# Adafrruit_PCF8523_QT.net
KiCad netlist of a schematic drawn in EAGLE
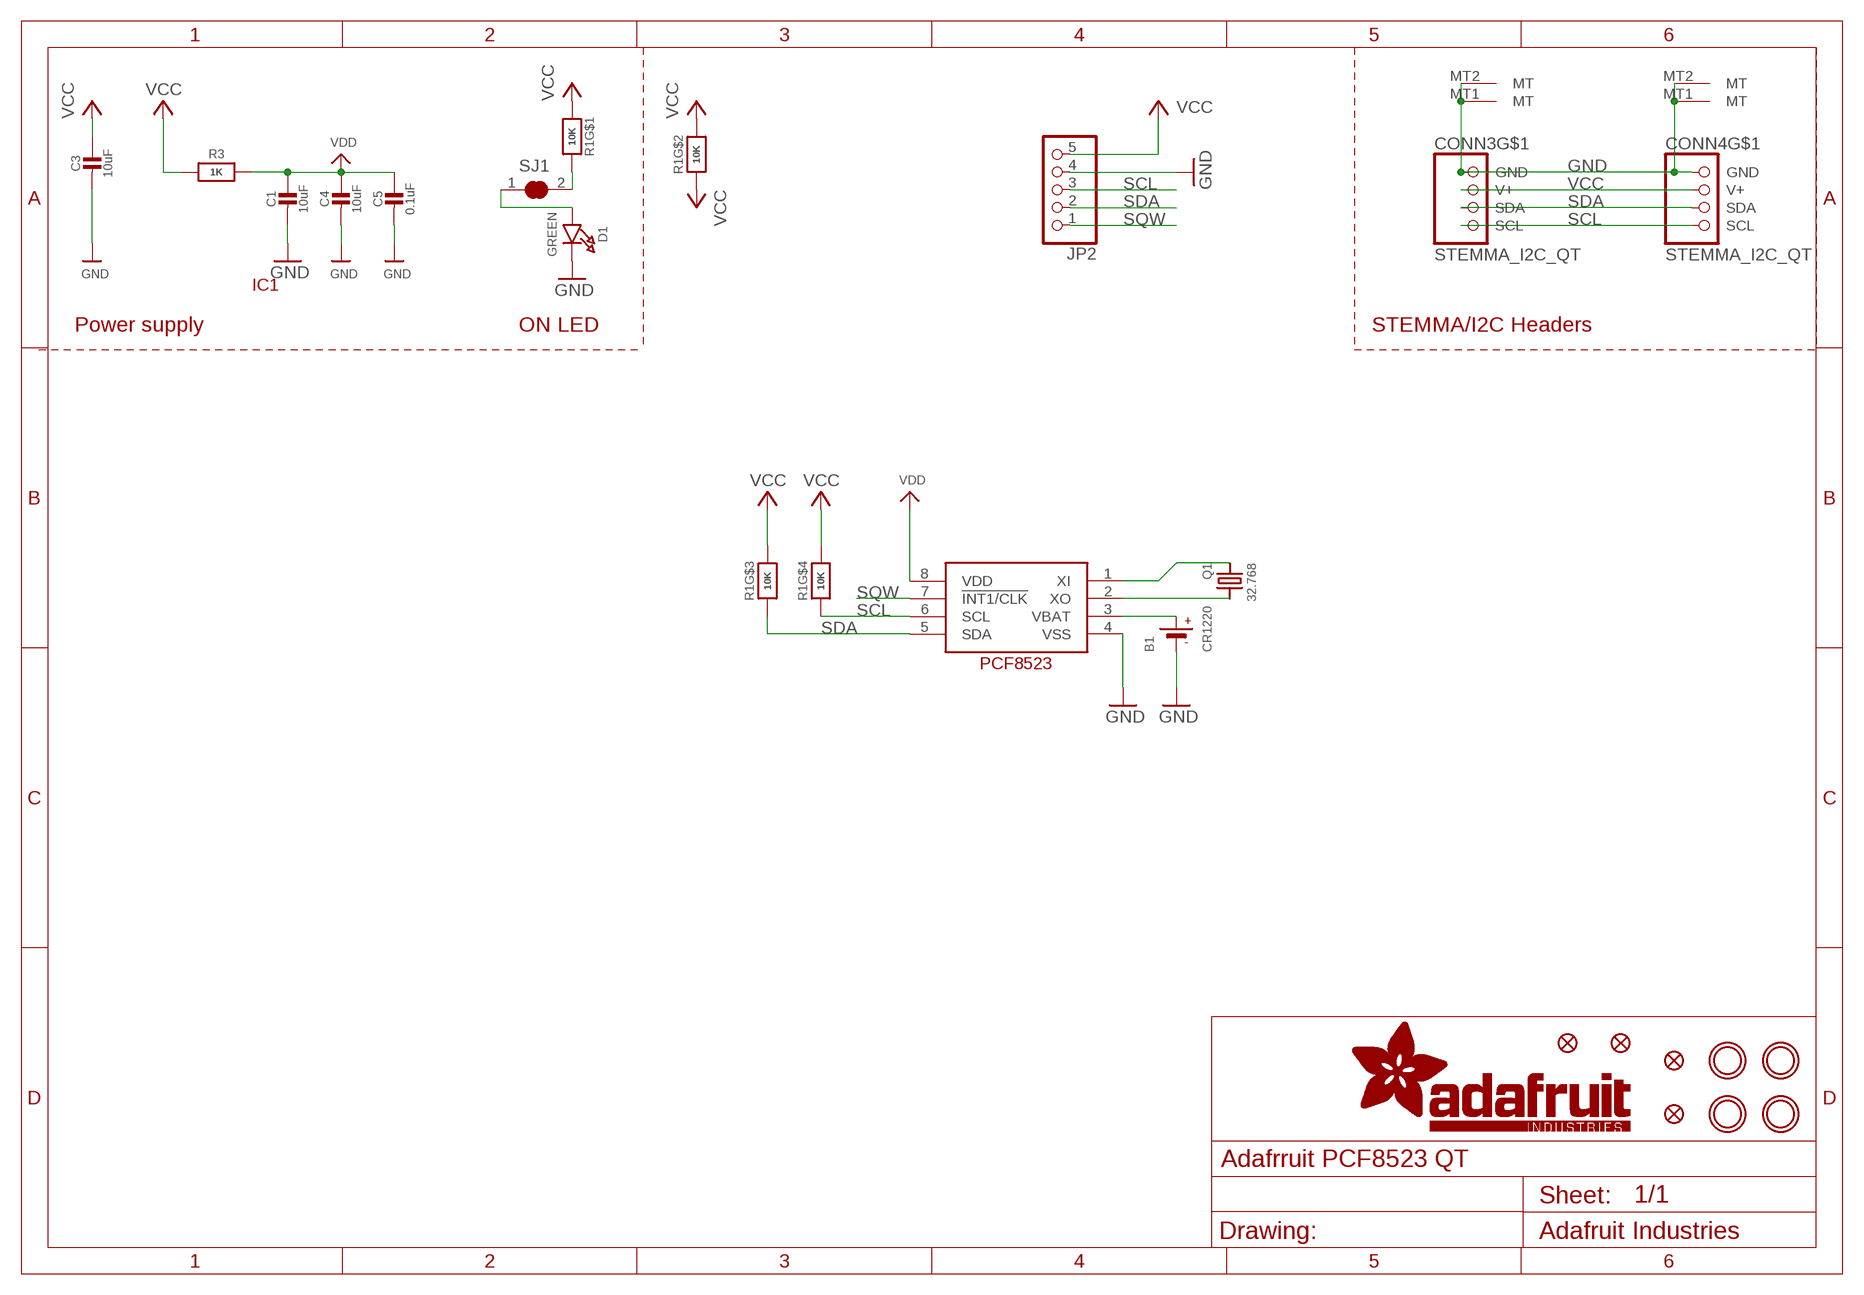
[diagram p0: schematic, sheet 1]

(export (version "E")
  (design (tool "Eeschema 10.0.6"))
  (components
    (comp (ref "B1")
      (value "CR1220")
      (footprint "eagle-import:CR1220")
      (libsource (lib "eagle-import") (part "BATTERYCR1220_SMT"))
    )
    (comp (ref "C1")
      (value "10uF")
      (footprint "eagle-import:0805-NO")
      (libsource (lib "eagle-import") (part "CAP_CERAMIC0805-NOOUTLINE"))
    )
    (comp (ref "C3")
      (value "10uF")
      (footprint "eagle-import:0805-NO")
      (libsource (lib "eagle-import") (part "CAP_CERAMIC0805-NOOUTLINE"))
    )
    (comp (ref "C4")
      (value "10uF")
      (footprint "eagle-import:0805-NO")
      (libsource (lib "eagle-import") (part "CAP_CERAMIC0805-NOOUTLINE"))
    )
    (comp (ref "C5")
      (value "0.1uF")
      (footprint "eagle-import:0603-NO")
      (libsource (lib "eagle-import") (part "CAP_CERAMIC0603_NO"))
    )
    (comp (ref "CONN3")
      (value "STEMMA_I2C_QT")
      (footprint "eagle-import:JST_SH4")
      (libsource (lib "eagle-import") (part "STEMMA_I2C_QT"))
    )
    (comp (ref "CONN4")
      (value "STEMMA_I2C_QT")
      (footprint "eagle-import:JST_SH4")
      (libsource (lib "eagle-import") (part "STEMMA_I2C_QT"))
    )
    (comp (ref "D1")
      (value "GREEN")
      (footprint "eagle-import:CHIPLED_0603_NOOUTLINE")
      (libsource (lib "eagle-import") (part "LED0603_NOOUTLINE"))
    )
    (comp (ref "FID1")
      (value "FIDUCIAL_1MM")
      (footprint "eagle-import:FIDUCIAL_1MM")
      (libsource (lib "eagle-import") (part "FIDUCIAL_1MM"))
    )
    (comp (ref "FID2")
      (value "FIDUCIAL_1MM")
      (footprint "eagle-import:FIDUCIAL_1MM")
      (libsource (lib "eagle-import") (part "FIDUCIAL_1MM"))
    )
    (comp (ref "FID3")
      (value "FIDUCIAL_1MM")
      (footprint "eagle-import:FIDUCIAL_1MM")
      (libsource (lib "eagle-import") (part "FIDUCIAL_1MM"))
    )
    (comp (ref "FID4")
      (value "FIDUCIAL_1MM")
      (footprint "eagle-import:FIDUCIAL_1MM")
      (libsource (lib "eagle-import") (part "FIDUCIAL_1MM"))
    )
    (comp (ref "IC1")
      (value "RTC_PCF8523T")
      (footprint "eagle-import:SOIC8_150MIL")
      (libsource (lib "eagle-import") (part "RTC_PCF8523T"))
    )
    (comp (ref "JP2")
      (value "HEADER-1X570MIL")
      (footprint "eagle-import:1X05_ROUND_70")
      (libsource (lib "eagle-import") (part "HEADER-1X570MIL"))
    )
    (comp (ref "Q1")
      (value "32.768")
      (footprint "eagle-import:XTAL3215")
      (libsource (lib "eagle-import") (part "CRYSTAL_3215"))
    )
    (comp (ref "R1")
      (value "10K")
      (footprint "eagle-import:RESPACK_4X0603")
      (libsource (lib "eagle-import") (part "RESISTOR_4PACK"))
    )
    (comp (ref "R3")
      (value "1K")
      (footprint "eagle-import:0603-NO")
      (libsource (lib "eagle-import") (part "RESISTOR_0603_NOOUT"))
    )
    (comp (ref "SJ1")
      (value "SOLDERJUMPER_CLOSED")
      (footprint "eagle-import:SOLDERJUMPER_CLOSEDWIRE")
      (libsource (lib "eagle-import") (part "SOLDERJUMPER_CLOSED"))
    )
    (comp (ref "U$9")
      (value "MOUNTINGHOLE3.0THIN")
      (footprint "eagle-import:MOUNTINGHOLE_3.0_PLATEDTHIN")
      (libsource (lib "eagle-import") (part "MOUNTINGHOLE3.0THIN"))
    )
    (comp (ref "U$17")
      (value "MOUNTINGHOLE3.0THIN")
      (footprint "eagle-import:MOUNTINGHOLE_3.0_PLATEDTHIN")
      (libsource (lib "eagle-import") (part "MOUNTINGHOLE3.0THIN"))
    )
    (comp (ref "U$19")
      (value "MOUNTINGHOLE3.0THIN")
      (footprint "eagle-import:MOUNTINGHOLE_3.0_PLATEDTHIN")
      (libsource (lib "eagle-import") (part "MOUNTINGHOLE3.0THIN"))
    )
    (comp (ref "U$21")
      (value "MOUNTINGHOLE3.0THIN")
      (footprint "eagle-import:MOUNTINGHOLE_3.0_PLATEDTHIN")
      (libsource (lib "eagle-import") (part "MOUNTINGHOLE3.0THIN"))
    )
  )
  (nets
    (net (code "1") (name "/SCL") (class "Default")
      (node (ref "CONN3") (pin "4") (pinfunction "SCL_4") (pintype "passive"))
      (node (ref "CONN4") (pin "4") (pinfunction "SCL_4") (pintype "passive"))
      (node (ref "IC1") (pin "6") (pinfunction "SCL_6") (pintype "bidirectional"))
      (node (ref "JP2") (pin "3") (pinfunction "3_3") (pintype "passive"))
      (node (ref "R1") (pin "4") (pinfunction "1_4") (pintype "passive"))
    )
    (net (code "2") (name "/SDA") (class "Default")
      (node (ref "CONN3") (pin "3") (pinfunction "SDA_3") (pintype "passive"))
      (node (ref "CONN4") (pin "3") (pinfunction "SDA_3") (pintype "passive"))
      (node (ref "IC1") (pin "5") (pinfunction "SDA_5") (pintype "bidirectional"))
      (node (ref "JP2") (pin "2") (pinfunction "2_2") (pintype "passive"))
      (node (ref "R1") (pin "3") (pinfunction "1_3") (pintype "passive"))
    )
    (net (code "3") (name "/SQW") (class "Default")
      (node (ref "IC1") (pin "7") (pinfunction "~{INT1/CLK}_7") (pintype "output"))
      (node (ref "JP2") (pin "1") (pinfunction "1_1") (pintype "passive"))
    )
    (net (code "4") (name "GND") (class "Default")
      (node (ref "B1") (pin "-") (pinfunction "-_-") (pintype "passive"))
      (node (ref "C1") (pin "2") (pinfunction "2_2") (pintype "passive"))
      (node (ref "C3") (pin "2") (pinfunction "2_2") (pintype "passive"))
      (node (ref "C4") (pin "2") (pinfunction "2_2") (pintype "passive"))
      (node (ref "C5") (pin "2") (pinfunction "2_2") (pintype "passive"))
      (node (ref "CONN3") (pin "1") (pinfunction "GND_1") (pintype "passive"))
      (node (ref "CONN3") (pin "MT1") (pinfunction "MT_MT1") (pintype "bidirectional"))
      (node (ref "CONN3") (pin "MT2") (pinfunction "MT_MT2") (pintype "bidirectional"))
      (node (ref "CONN4") (pin "1") (pinfunction "GND_1") (pintype "passive"))
      (node (ref "CONN4") (pin "MT1") (pinfunction "MT_MT1") (pintype "bidirectional"))
      (node (ref "CONN4") (pin "MT2") (pinfunction "MT_MT2") (pintype "bidirectional"))
      (node (ref "D1") (pin "C") (pinfunction "C_C") (pintype "passive"))
      (node (ref "IC1") (pin "4") (pinfunction "VSS_4") (pintype "power_in"))
      (node (ref "JP2") (pin "4") (pinfunction "4_4") (pintype "passive"))
    )
    (net (code "5") (name "Net-(D1-PadA)") (class "Default")
      (node (ref "D1") (pin "A") (pinfunction "A_A") (pintype "passive"))
      (node (ref "SJ1") (pin "1") (pinfunction "1_1") (pintype "passive"))
    )
    (net (code "6") (name "Net-(IC1-VBAT)") (class "Default")
      (node (ref "B1") (pin "+$1") (pinfunction "+_+$1") (pintype "passive"))
      (node (ref "B1") (pin "+$2") (pinfunction "+_+$2") (pintype "passive"))
      (node (ref "IC1") (pin "3") (pinfunction "VBAT_3") (pintype "power_in"))
    )
    (net (code "7") (name "Net-(IC1-XI)") (class "Default")
      (node (ref "IC1") (pin "1") (pinfunction "XI_1") (pintype "input"))
      (node (ref "Q1") (pin "P$1") (pinfunction "1_P$1") (pintype "passive"))
    )
    (net (code "8") (name "Net-(IC1-XO)") (class "Default")
      (node (ref "IC1") (pin "2") (pinfunction "XO_2") (pintype "output"))
      (node (ref "Q1") (pin "P$2") (pinfunction "2_P$2") (pintype "passive"))
    )
    (net (code "9") (name "Net-(R1A-2)") (class "Default")
      (node (ref "R1") (pin "8") (pinfunction "2_8") (pintype "passive"))
      (node (ref "SJ1") (pin "2") (pinfunction "2_2") (pintype "passive"))
    )
    (net (code "10") (name "VCC") (class "Default")
      (node (ref "C3") (pin "1") (pinfunction "1_1") (pintype "passive"))
      (node (ref "CONN3") (pin "2") (pinfunction "V+_2") (pintype "passive"))
      (node (ref "CONN4") (pin "2") (pinfunction "V+_2") (pintype "passive"))
      (node (ref "JP2") (pin "5") (pinfunction "5_5") (pintype "passive"))
      (node (ref "R1") (pin "1") (pinfunction "1_1") (pintype "passive"))
      (node (ref "R1") (pin "2") (pinfunction "1_2") (pintype "passive"))
      (node (ref "R1") (pin "5") (pinfunction "2_5") (pintype "passive"))
      (node (ref "R1") (pin "6") (pinfunction "2_6") (pintype "passive"))
      (node (ref "R1") (pin "7") (pinfunction "2_7") (pintype "passive"))
      (node (ref "R3") (pin "1") (pinfunction "1_1") (pintype "passive"))
    )
    (net (code "11") (name "VDD") (class "Default")
      (node (ref "C1") (pin "1") (pinfunction "1_1") (pintype "passive"))
      (node (ref "C4") (pin "1") (pinfunction "1_1") (pintype "passive"))
      (node (ref "C5") (pin "1") (pinfunction "1_1") (pintype "passive"))
      (node (ref "IC1") (pin "8") (pinfunction "VDD_8") (pintype "power_in"))
      (node (ref "R3") (pin "2") (pinfunction "2_2") (pintype "passive"))
    )
  )
)
